# team13.net
KiCad netlist of a schematic drawn in EAGLE
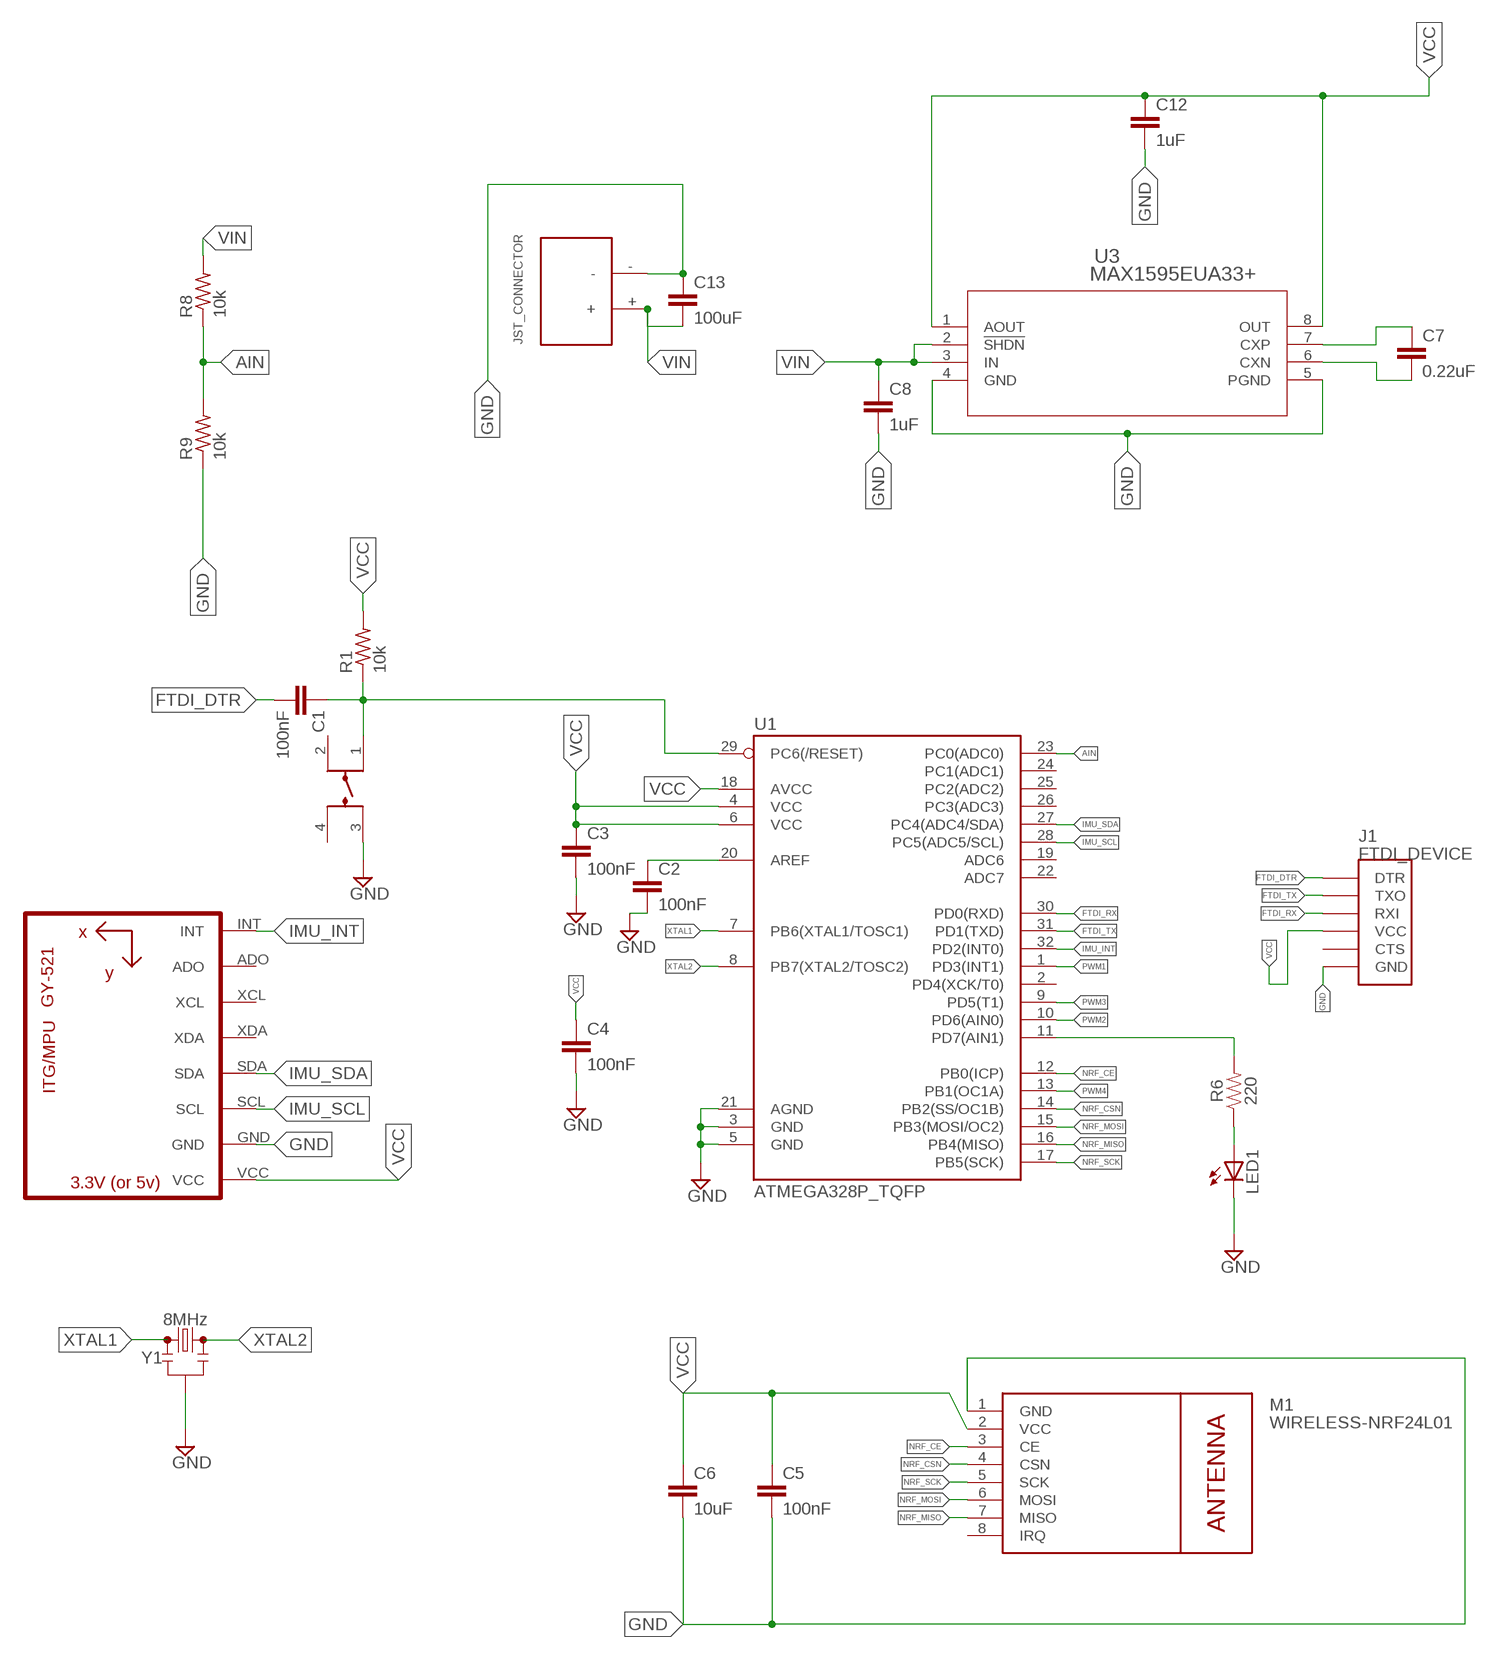
[diagram p0: schematic, sheet 1, part 1 of 3]
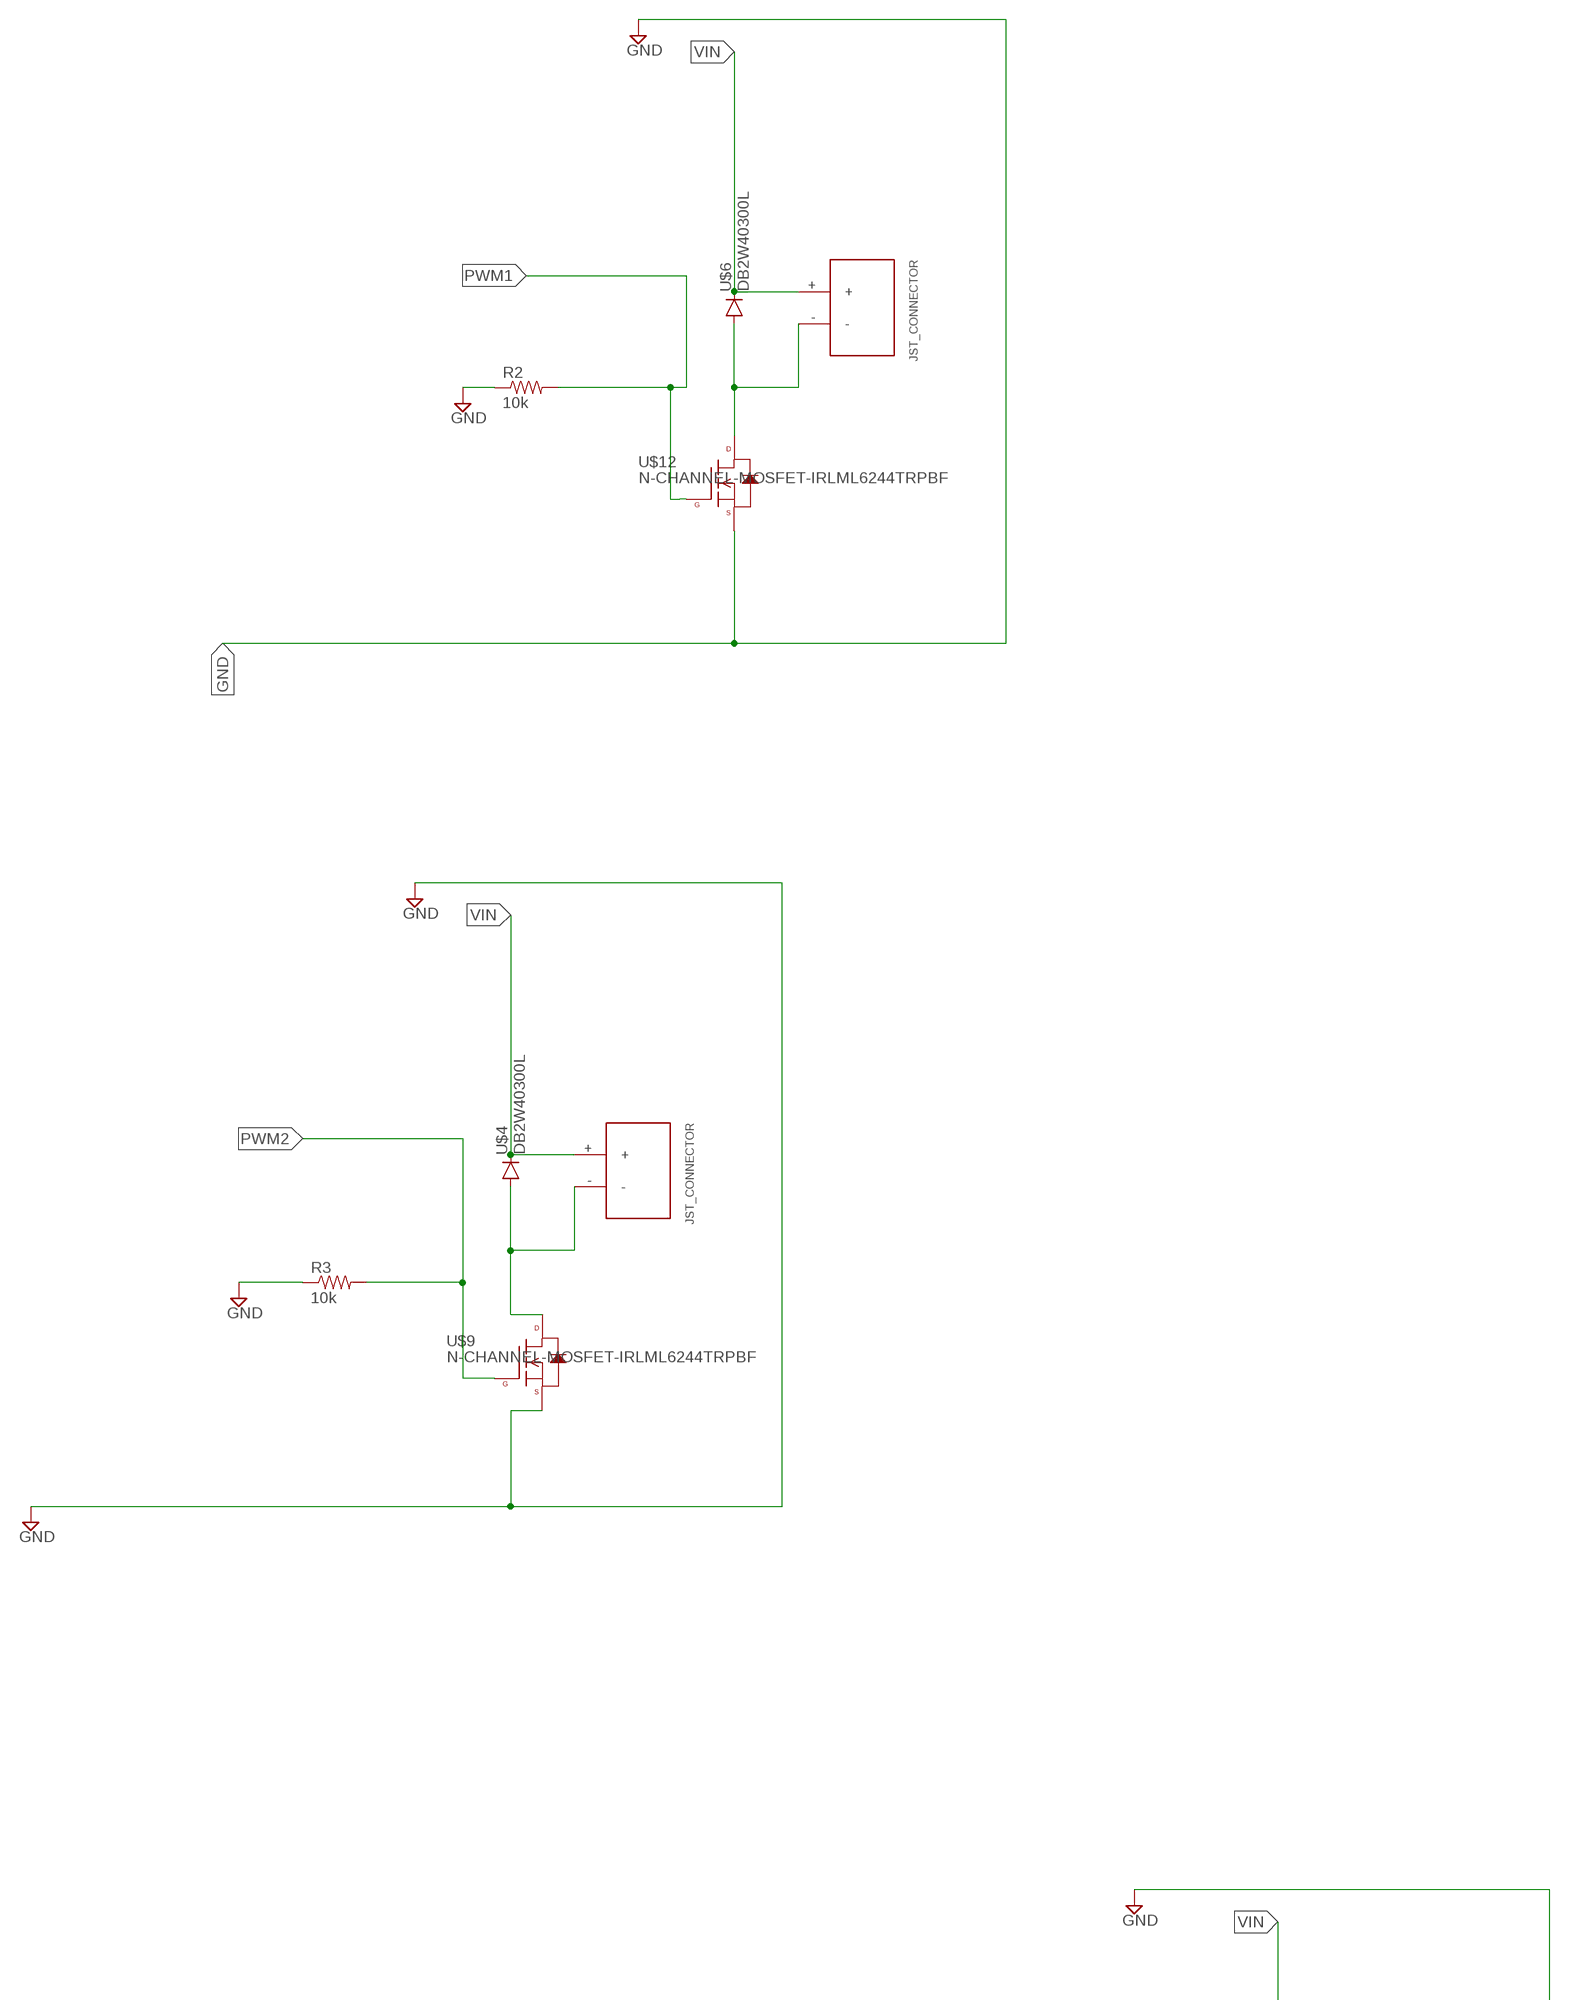
[diagram p1: schematic, sheet 1, part 2 of 3]
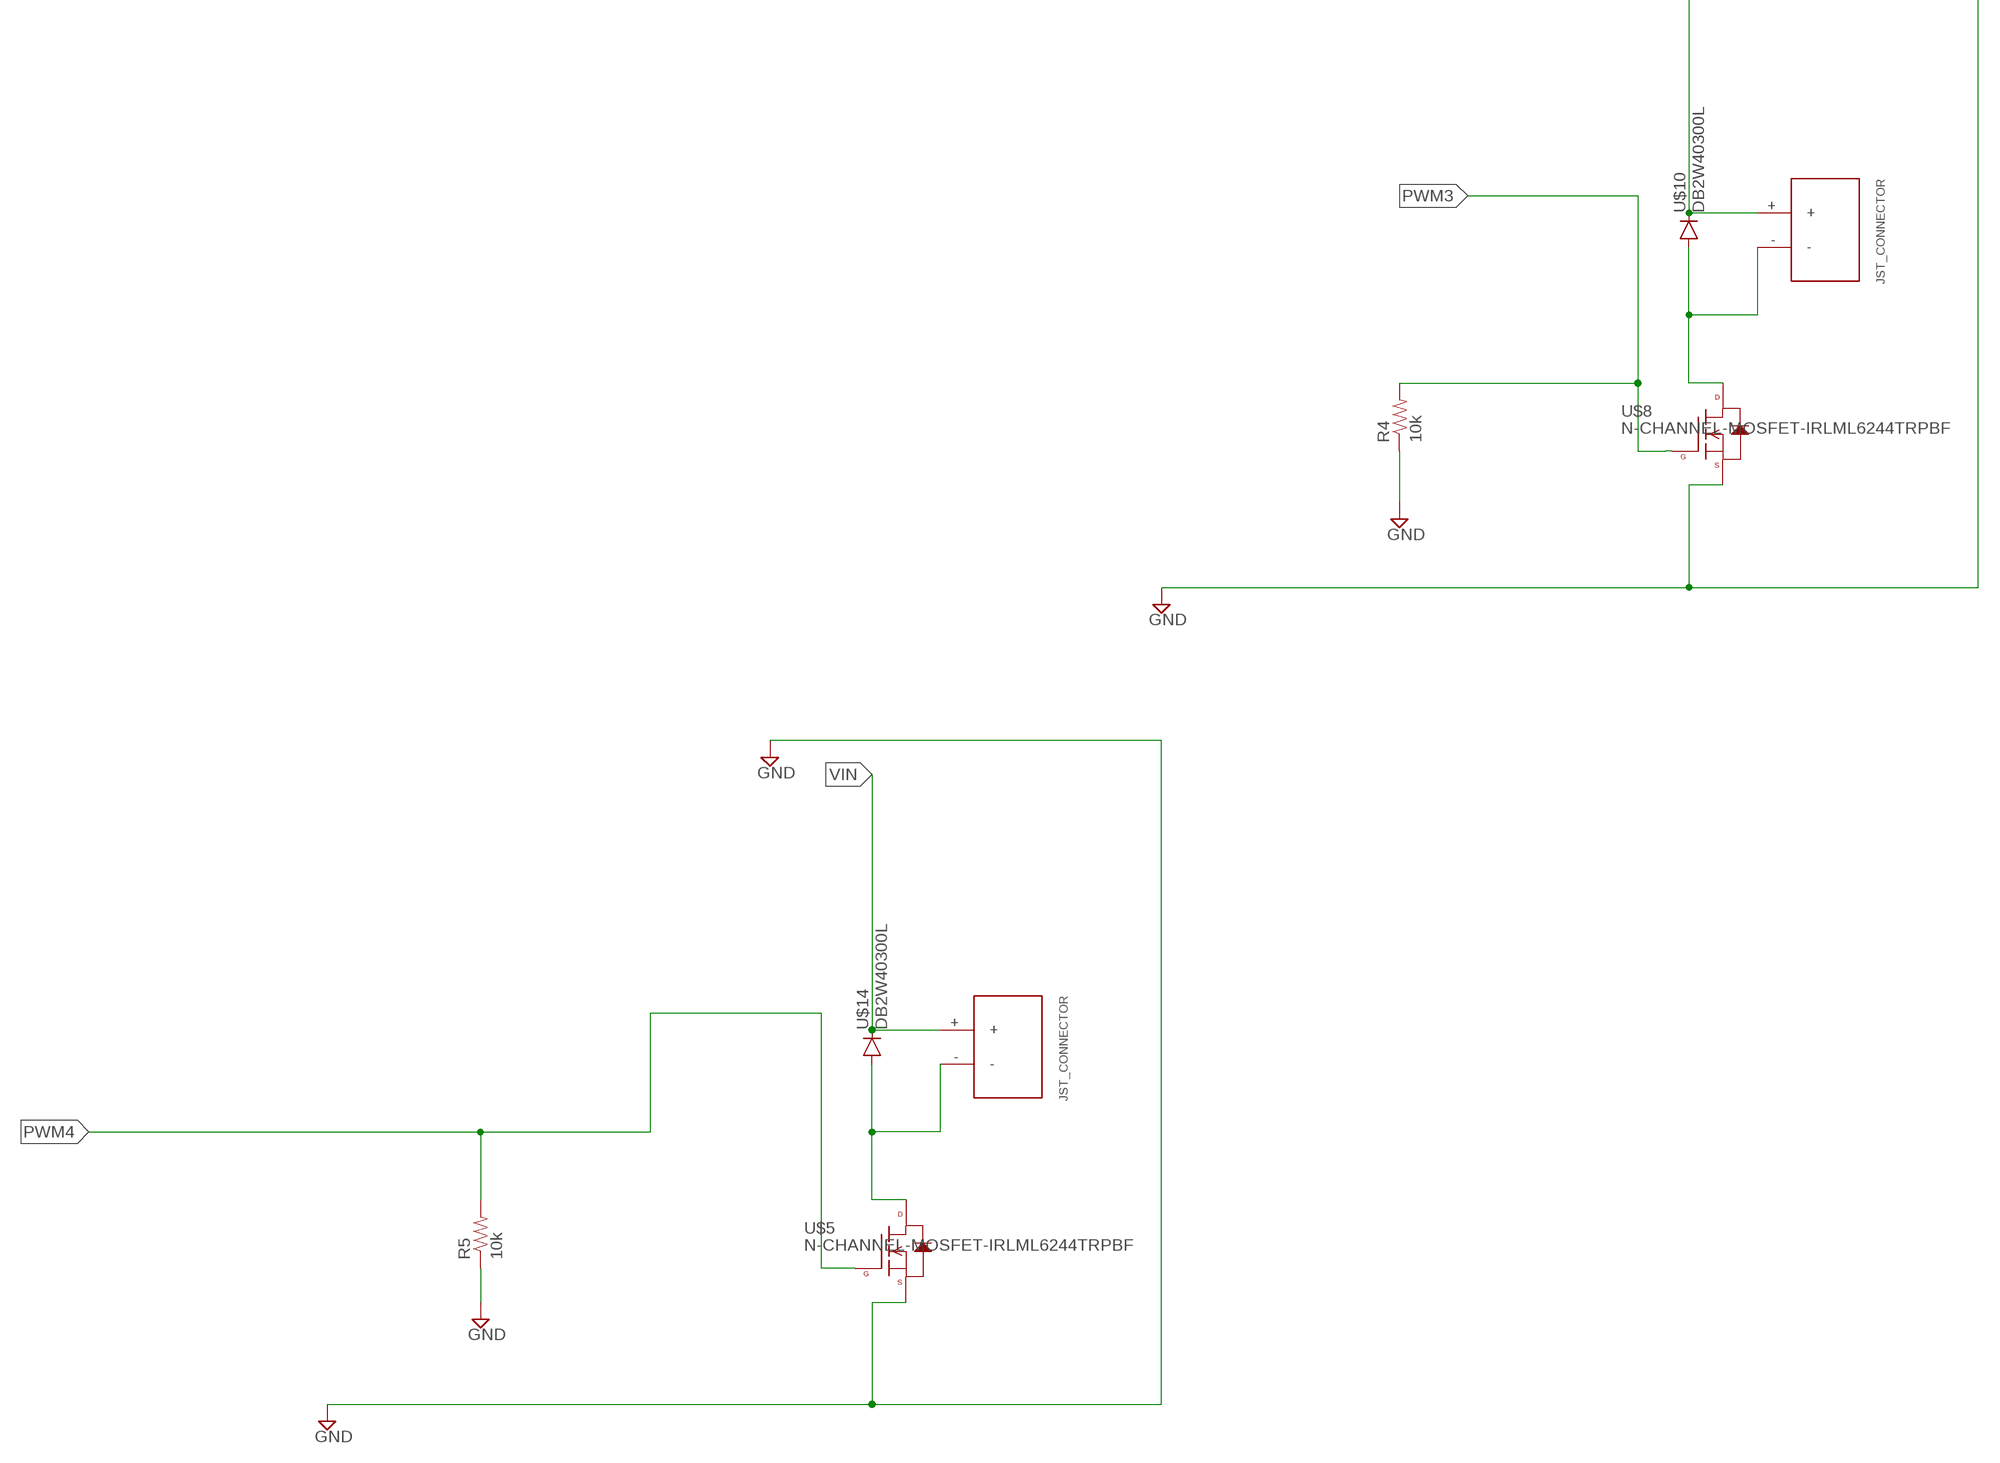
[diagram p2: schematic, sheet 1, part 3 of 3]

(export (version "E")
  (design (tool "Eeschema 10.0.6"))
  (components
    (comp (ref "C1")
      (value "100nF")
      (footprint "eagle-import:C0603")
      (libsource (lib "eagle-import") (part "C-EUC0603"))
    )
    (comp (ref "C2")
      (value "100nF")
      (footprint "eagle-import:C0603")
      (libsource (lib "eagle-import") (part "C-EUC0603"))
    )
    (comp (ref "C3")
      (value "100nF")
      (footprint "eagle-import:C0603")
      (libsource (lib "eagle-import") (part "C-EUC0603"))
    )
    (comp (ref "C4")
      (value "100nF")
      (footprint "eagle-import:C0603")
      (libsource (lib "eagle-import") (part "C-EUC0603"))
    )
    (comp (ref "C5")
      (value "100nF")
      (footprint "eagle-import:C0603")
      (libsource (lib "eagle-import") (part "C-EUC0603"))
    )
    (comp (ref "C6")
      (value "10uF")
      (footprint "eagle-import:C0603")
      (libsource (lib "eagle-import") (part "C-EUC0603"))
    )
    (comp (ref "C7")
      (value "0.22uF")
      (footprint "eagle-import:C0603")
      (libsource (lib "eagle-import") (part "C-EUC0603"))
    )
    (comp (ref "C8")
      (value "1uF")
      (footprint "eagle-import:C0603")
      (libsource (lib "eagle-import") (part "C-EUC0603"))
    )
    (comp (ref "C12")
      (value "1uF")
      (footprint "eagle-import:C0603")
      (libsource (lib "eagle-import") (part "C-EUC0603"))
    )
    (comp (ref "C13")
      (value "100uF")
      (footprint "eagle-import:C1206")
      (libsource (lib "eagle-import") (part "C-EUC1206"))
    )
    (comp (ref "J1")
      (value "FTDI_DEVICE")
      (footprint "eagle-import:FTDI_DEVICE_SIDE")
      (libsource (lib "eagle-import") (part "FTDI_DEVICE"))
    )
    (comp (ref "LED1")
      (value "LED1206")
      (footprint "eagle-import:LED-1206")
      (libsource (lib "eagle-import") (part "LED1206"))
    )
    (comp (ref "M1")
      (value "WIRELESS-NRF24L01")
      (footprint "eagle-import:WIRELESS-NRF24L01")
      (libsource (lib "eagle-import") (part "WIRELESS-NRF24L01"))
    )
    (comp (ref "R1")
      (value "10k")
      (footprint "eagle-import:R0603")
      (libsource (lib "eagle-import") (part "R-US_R0603"))
    )
    (comp (ref "R2")
      (value "10k")
      (footprint "eagle-import:0603-RES")
      (libsource (lib "eagle-import") (part "RESISTOR0603"))
    )
    (comp (ref "R3")
      (value "10k")
      (footprint "eagle-import:0603-RES")
      (libsource (lib "eagle-import") (part "RESISTOR0603"))
    )
    (comp (ref "R4")
      (value "10k")
      (footprint "eagle-import:0603-RES")
      (libsource (lib "eagle-import") (part "RESISTOR0603"))
    )
    (comp (ref "R5")
      (value "10k")
      (footprint "eagle-import:0603-RES")
      (libsource (lib "eagle-import") (part "RESISTOR0603"))
    )
    (comp (ref "R6")
      (value "220")
      (footprint "eagle-import:0603")
      (libsource (lib "eagle-import") (part "220OHM-0603-1/10W-1%"))
    )
    (comp (ref "R8")
      (value "10k")
      (footprint "eagle-import:R0603")
      (libsource (lib "eagle-import") (part "R-US_R0603"))
    )
    (comp (ref "R9")
      (value "10k")
      (footprint "eagle-import:R0603")
      (libsource (lib "eagle-import") (part "R-US_R0603"))
    )
    (comp (ref "U$1")
      (value "LL3301NF065QG")
      (footprint "eagle-import:LL3301NF065QG")
      (libsource (lib "eagle-import") (part "LL3301NF065QG"))
    )
    (comp (ref "U$3")
      (value "JST_CONNECTOR_FEMALE")
      (footprint "eagle-import:JST_CONNECTOR_FEMALE")
      (libsource (lib "eagle-import") (part "JST_CONNECTOR_FEMALE"))
    )
    (comp (ref "U$4")
      (value "DB2W40300L")
      (footprint "eagle-import:MINI2-F3-B")
      (libsource (lib "eagle-import") (part "DB2W40300L"))
    )
    (comp (ref "U$5")
      (value "N-CHANNEL-MOSFET-IRLML6244TRPBF")
      (footprint "eagle-import:SOT23-3")
      (libsource (lib "eagle-import") (part "N-CHANNEL-MOSFET-IRLML6244TRPBF"))
    )
    (comp (ref "U$6")
      (value "DB2W40300L")
      (footprint "eagle-import:MINI2-F3-B")
      (libsource (lib "eagle-import") (part "DB2W40300L"))
    )
    (comp (ref "U$7")
      (value "JST_CONNECTOR_FEMALE")
      (footprint "eagle-import:JST_CONNECTOR_FEMALE")
      (libsource (lib "eagle-import") (part "JST_CONNECTOR_FEMALE"))
    )
    (comp (ref "U$8")
      (value "N-CHANNEL-MOSFET-IRLML6244TRPBF")
      (footprint "eagle-import:SOT23-3")
      (libsource (lib "eagle-import") (part "N-CHANNEL-MOSFET-IRLML6244TRPBF"))
    )
    (comp (ref "U$9")
      (value "N-CHANNEL-MOSFET-IRLML6244TRPBF")
      (footprint "eagle-import:SOT23-3")
      (libsource (lib "eagle-import") (part "N-CHANNEL-MOSFET-IRLML6244TRPBF"))
    )
    (comp (ref "U$10")
      (value "DB2W40300L")
      (footprint "eagle-import:MINI2-F3-B")
      (libsource (lib "eagle-import") (part "DB2W40300L"))
    )
    (comp (ref "U$11")
      (value "JST_CONNECTOR_FEMALE")
      (footprint "eagle-import:JST_CONNECTOR_FEMALE")
      (libsource (lib "eagle-import") (part "JST_CONNECTOR_FEMALE"))
    )
    (comp (ref "U$12")
      (value "N-CHANNEL-MOSFET-IRLML6244TRPBF")
      (footprint "eagle-import:SOT23-3")
      (libsource (lib "eagle-import") (part "N-CHANNEL-MOSFET-IRLML6244TRPBF"))
    )
    (comp (ref "U$14")
      (value "DB2W40300L")
      (footprint "eagle-import:MINI2-F3-B")
      (libsource (lib "eagle-import") (part "DB2W40300L"))
    )
    (comp (ref "U$15")
      (value "JST_CONNECTOR_FEMALE")
      (footprint "eagle-import:JST_CONNECTOR_FEMALE")
      (libsource (lib "eagle-import") (part "JST_CONNECTOR_FEMALE"))
    )
    (comp (ref "U$19")
      (value "JST_CONNECTOR_FEMALE")
      (footprint "eagle-import:JST_CONNECTOR_FEMALE")
      (libsource (lib "eagle-import") (part "JST_CONNECTOR_FEMALE"))
    )
    (comp (ref "U1")
      (value "ATMEGA328P_TQFP")
      (footprint "eagle-import:TQFP32-08")
      (libsource (lib "eagle-import") (part "ATMEGA328P_TQFP"))
    )
    (comp (ref "U2")
      (value "GY-521MPU6050")
      (footprint "eagle-import:GY-521")
      (libsource (lib "eagle-import") (part "GY-521MPU6050"))
    )
    (comp (ref "U3")
      (value "MAX1595EUA33+")
      (footprint "eagle-import:21-0036K")
      (libsource (lib "eagle-import") (part "MAX1595EUA33+"))
    )
    (comp (ref "Y1")
      (value "8MHz")
      (footprint "eagle-import:RESONATOR-SMD-3.2X1.3")
      (libsource (lib "eagle-import") (part "RESONATOR-8MHZSMD_3.2X1.3"))
    )
  )
  (nets
    (net (code "1") (name "AIN") (class "Default")
      (node (ref "R8") (pin "1") (pinfunction "1_1") (pintype "passive"))
      (node (ref "R9") (pin "2") (pinfunction "2_2") (pintype "passive"))
      (node (ref "U1") (pin "23") (pinfunction "PC0(ADC0)_23") (pintype "bidirectional"))
    )
    (net (code "2") (name "FTDI_DTR") (class "Default")
      (node (ref "C1") (pin "2") (pinfunction "2_2") (pintype "passive"))
      (node (ref "J1") (pin "P$1") (pinfunction "DTR_P$1") (pintype "bidirectional"))
    )
    (net (code "3") (name "FTDI_RX") (class "Default")
      (node (ref "J1") (pin "P$3") (pinfunction "RXI_P$3") (pintype "bidirectional"))
      (node (ref "U1") (pin "30") (pinfunction "PD0(RXD)_30") (pintype "bidirectional"))
    )
    (net (code "4") (name "FTDI_TX") (class "Default")
      (node (ref "J1") (pin "P$2") (pinfunction "TXO_P$2") (pintype "bidirectional"))
      (node (ref "U1") (pin "31") (pinfunction "PD1(TXD)_31") (pintype "bidirectional"))
    )
    (net (code "5") (name "GND") (class "Default")
      (node (ref "C12") (pin "2") (pinfunction "2_2") (pintype "passive"))
      (node (ref "C13") (pin "1") (pinfunction "1_1") (pintype "passive"))
      (node (ref "C2") (pin "2") (pinfunction "2_2") (pintype "passive"))
      (node (ref "C3") (pin "2") (pinfunction "2_2") (pintype "passive"))
      (node (ref "C4") (pin "2") (pinfunction "2_2") (pintype "passive"))
      (node (ref "C5") (pin "2") (pinfunction "2_2") (pintype "passive"))
      (node (ref "C6") (pin "2") (pinfunction "2_2") (pintype "passive"))
      (node (ref "C8") (pin "2") (pinfunction "2_2") (pintype "passive"))
      (node (ref "J1") (pin "P$6") (pinfunction "GND_P$6") (pintype "bidirectional"))
      (node (ref "LED1") (pin "C") (pinfunction "C_C") (pintype "passive"))
      (node (ref "M1") (pin "1") (pinfunction "GND_1") (pintype "power_in"))
      (node (ref "R2") (pin "1") (pinfunction "1_1") (pintype "passive"))
      (node (ref "R3") (pin "1") (pinfunction "1_1") (pintype "passive"))
      (node (ref "R4") (pin "1") (pinfunction "1_1") (pintype "passive"))
      (node (ref "R5") (pin "1") (pinfunction "1_1") (pintype "passive"))
      (node (ref "R9") (pin "1") (pinfunction "1_1") (pintype "passive"))
      (node (ref "U$1") (pin "3") (pinfunction "3_3") (pintype "passive"))
      (node (ref "U$12") (pin "2") (pinfunction "S_2") (pintype "passive"))
      (node (ref "U$19") (pin "-") (pinfunction "-_-") (pintype "bidirectional"))
      (node (ref "U$5") (pin "2") (pinfunction "S_2") (pintype "passive"))
      (node (ref "U$8") (pin "2") (pinfunction "S_2") (pintype "passive"))
      (node (ref "U$9") (pin "2") (pinfunction "S_2") (pintype "passive"))
      (node (ref "U1") (pin "21") (pinfunction "AGND_21") (pintype "bidirectional"))
      (node (ref "U1") (pin "3") (pinfunction "GND_3") (pintype "bidirectional"))
      (node (ref "U1") (pin "5") (pinfunction "GND_5") (pintype "bidirectional"))
      (node (ref "U2") (pin "GND") (pinfunction "GND_GND") (pintype "bidirectional"))
      (node (ref "U3") (pin "4") (pinfunction "GND_4") (pintype "power_in"))
      (node (ref "U3") (pin "5") (pinfunction "PGND_5") (pintype "passive"))
      (node (ref "Y1") (pin "2") (pinfunction "2_2") (pintype "passive"))
    )
    (net (code "6") (name "IMU_INT") (class "Default")
      (node (ref "U1") (pin "32") (pinfunction "PD2(INT0)_32") (pintype "bidirectional"))
      (node (ref "U2") (pin "INT") (pinfunction "INT_INT") (pintype "bidirectional"))
    )
    (net (code "7") (name "IMU_SCL") (class "Default")
      (node (ref "U1") (pin "28") (pinfunction "PC5(ADC5/SCL)_28") (pintype "bidirectional"))
      (node (ref "U2") (pin "SCL") (pinfunction "SCL_SCL") (pintype "bidirectional"))
    )
    (net (code "8") (name "IMU_SDA") (class "Default")
      (node (ref "U1") (pin "27") (pinfunction "PC4(ADC4/SDA)_27") (pintype "bidirectional"))
      (node (ref "U2") (pin "SDA") (pinfunction "SDA_SDA") (pintype "bidirectional"))
    )
    (net (code "9") (name "NRF_CE") (class "Default")
      (node (ref "M1") (pin "3") (pinfunction "CE_3") (pintype "bidirectional"))
      (node (ref "U1") (pin "12") (pinfunction "PB0(ICP)_12") (pintype "bidirectional"))
    )
    (net (code "10") (name "NRF_CSN") (class "Default")
      (node (ref "M1") (pin "4") (pinfunction "CSN_4") (pintype "bidirectional"))
      (node (ref "U1") (pin "14") (pinfunction "PB2(SS/OC1B)_14") (pintype "bidirectional"))
    )
    (net (code "11") (name "NRF_MISO") (class "Default")
      (node (ref "M1") (pin "7") (pinfunction "MISO_7") (pintype "bidirectional"))
      (node (ref "U1") (pin "16") (pinfunction "PB4(MISO)_16") (pintype "bidirectional"))
    )
    (net (code "12") (name "NRF_MOSI") (class "Default")
      (node (ref "M1") (pin "6") (pinfunction "MOSI_6") (pintype "bidirectional"))
      (node (ref "U1") (pin "15") (pinfunction "PB3(MOSI/OC2)_15") (pintype "bidirectional"))
    )
    (net (code "13") (name "NRF_SCK") (class "Default")
      (node (ref "M1") (pin "5") (pinfunction "SCK_5") (pintype "bidirectional"))
      (node (ref "U1") (pin "17") (pinfunction "PB5(SCK)_17") (pintype "bidirectional"))
    )
    (net (code "14") (name "Net-(LED1-PadA)") (class "Default")
      (node (ref "LED1") (pin "A") (pinfunction "A_A") (pintype "passive"))
      (node (ref "R6") (pin "1") (pinfunction "1_1") (pintype "passive"))
    )
    (net (code "15") (name "Net-(U$4-PPIN)") (class "Default")
      (node (ref "U$3") (pin "-") (pinfunction "-_-") (pintype "bidirectional"))
      (node (ref "U$4") (pin "POS") (pinfunction "PPIN_POS") (pintype "passive"))
      (node (ref "U$9") (pin "3") (pinfunction "D_3") (pintype "passive"))
    )
    (net (code "16") (name "Net-(U$10-PPIN)") (class "Default")
      (node (ref "U$10") (pin "POS") (pinfunction "PPIN_POS") (pintype "passive"))
      (node (ref "U$11") (pin "-") (pinfunction "-_-") (pintype "bidirectional"))
      (node (ref "U$8") (pin "3") (pinfunction "D_3") (pintype "passive"))
    )
    (net (code "17") (name "Net-(U$12-D)") (class "Default")
      (node (ref "U$12") (pin "3") (pinfunction "D_3") (pintype "passive"))
      (node (ref "U$6") (pin "POS") (pinfunction "PPIN_POS") (pintype "passive"))
      (node (ref "U$7") (pin "-") (pinfunction "-_-") (pintype "bidirectional"))
    )
    (net (code "18") (name "Net-(U$14-PPIN)") (class "Default")
      (node (ref "U$14") (pin "POS") (pinfunction "PPIN_POS") (pintype "passive"))
      (node (ref "U$15") (pin "-") (pinfunction "-_-") (pintype "bidirectional"))
      (node (ref "U$5") (pin "3") (pinfunction "D_3") (pintype "passive"))
    )
    (net (code "19") (name "Net-(U1-AREF)") (class "Default")
      (node (ref "C2") (pin "1") (pinfunction "1_1") (pintype "passive"))
      (node (ref "U1") (pin "20") (pinfunction "AREF_20") (pintype "bidirectional"))
    )
    (net (code "20") (name "Net-(U1-PC6({slash}RESET))") (class "Default")
      (node (ref "C1") (pin "1") (pinfunction "1_1") (pintype "passive"))
      (node (ref "R1") (pin "1") (pinfunction "1_1") (pintype "passive"))
      (node (ref "U$1") (pin "1") (pinfunction "1_1") (pintype "passive"))
      (node (ref "U1") (pin "29") (pinfunction "PC6(/RESET)_29") (pintype "bidirectional"))
    )
    (net (code "21") (name "Net-(U1-PD7(AIN1))") (class "Default")
      (node (ref "R6") (pin "2") (pinfunction "2_2") (pintype "passive"))
      (node (ref "U1") (pin "11") (pinfunction "PD7(AIN1)_11") (pintype "bidirectional"))
    )
    (net (code "22") (name "Net-(U3-CXN)") (class "Default")
      (node (ref "C7") (pin "2") (pinfunction "2_2") (pintype "passive"))
      (node (ref "U3") (pin "6") (pinfunction "CXN_6") (pintype "passive"))
    )
    (net (code "23") (name "Net-(U3-CXP)") (class "Default")
      (node (ref "C7") (pin "1") (pinfunction "1_1") (pintype "passive"))
      (node (ref "U3") (pin "7") (pinfunction "CXP_7") (pintype "passive"))
    )
    (net (code "24") (name "PWM1") (class "Default")
      (node (ref "R2") (pin "2") (pinfunction "2_2") (pintype "passive"))
      (node (ref "U$12") (pin "1") (pinfunction "G_1") (pintype "passive"))
      (node (ref "U1") (pin "1") (pinfunction "PD3(INT1)_1") (pintype "bidirectional"))
    )
    (net (code "25") (name "PWM2") (class "Default")
      (node (ref "R3") (pin "2") (pinfunction "2_2") (pintype "passive"))
      (node (ref "U$9") (pin "1") (pinfunction "G_1") (pintype "passive"))
      (node (ref "U1") (pin "10") (pinfunction "PD6(AIN0)_10") (pintype "bidirectional"))
    )
    (net (code "26") (name "PWM3") (class "Default")
      (node (ref "R4") (pin "2") (pinfunction "2_2") (pintype "passive"))
      (node (ref "U$8") (pin "1") (pinfunction "G_1") (pintype "passive"))
      (node (ref "U1") (pin "9") (pinfunction "PD5(T1)_9") (pintype "bidirectional"))
    )
    (net (code "27") (name "PWM4") (class "Default")
      (node (ref "R5") (pin "2") (pinfunction "2_2") (pintype "passive"))
      (node (ref "U$5") (pin "1") (pinfunction "G_1") (pintype "passive"))
      (node (ref "U1") (pin "13") (pinfunction "PB1(OC1A)_13") (pintype "bidirectional"))
    )
    (net (code "28") (name "VCC") (class "Default")
      (node (ref "C12") (pin "1") (pinfunction "1_1") (pintype "passive"))
      (node (ref "C3") (pin "1") (pinfunction "1_1") (pintype "passive"))
      (node (ref "C4") (pin "1") (pinfunction "1_1") (pintype "passive"))
      (node (ref "C5") (pin "1") (pinfunction "1_1") (pintype "passive"))
      (node (ref "C6") (pin "1") (pinfunction "1_1") (pintype "passive"))
      (node (ref "J1") (pin "P$4") (pinfunction "VCC_P$4") (pintype "bidirectional"))
      (node (ref "M1") (pin "2") (pinfunction "VCC_2") (pintype "power_in"))
      (node (ref "R1") (pin "2") (pinfunction "2_2") (pintype "passive"))
      (node (ref "U1") (pin "18") (pinfunction "AVCC_18") (pintype "bidirectional"))
      (node (ref "U1") (pin "4") (pinfunction "VCC_4") (pintype "bidirectional"))
      (node (ref "U1") (pin "6") (pinfunction "VCC_6") (pintype "bidirectional"))
      (node (ref "U2") (pin "VCC") (pinfunction "VCC_VCC") (pintype "bidirectional"))
      (node (ref "U3") (pin "1") (pinfunction "AOUT_1") (pintype "passive"))
      (node (ref "U3") (pin "8") (pinfunction "OUT_8") (pintype "passive"))
    )
    (net (code "29") (name "VIN") (class "Default")
      (node (ref "C13") (pin "2") (pinfunction "2_2") (pintype "passive"))
      (node (ref "C8") (pin "1") (pinfunction "1_1") (pintype "passive"))
      (node (ref "R8") (pin "2") (pinfunction "2_2") (pintype "passive"))
      (node (ref "U$10") (pin "NEG") (pinfunction "GPIN_NEG") (pintype "passive"))
      (node (ref "U$11") (pin "+") (pinfunction "+_+") (pintype "bidirectional"))
      (node (ref "U$14") (pin "NEG") (pinfunction "GPIN_NEG") (pintype "passive"))
      (node (ref "U$15") (pin "+") (pinfunction "+_+") (pintype "bidirectional"))
      (node (ref "U$19") (pin "+") (pinfunction "+_+") (pintype "bidirectional"))
      (node (ref "U$3") (pin "+") (pinfunction "+_+") (pintype "bidirectional"))
      (node (ref "U$4") (pin "NEG") (pinfunction "GPIN_NEG") (pintype "passive"))
      (node (ref "U$6") (pin "NEG") (pinfunction "GPIN_NEG") (pintype "passive"))
      (node (ref "U$7") (pin "+") (pinfunction "+_+") (pintype "bidirectional"))
      (node (ref "U3") (pin "2") (pinfunction "~{SHDN}_2") (pintype "passive"))
      (node (ref "U3") (pin "3") (pinfunction "IN_3") (pintype "input"))
    )
    (net (code "30") (name "XTAL1") (class "Default")
      (node (ref "U1") (pin "7") (pinfunction "PB6(XTAL1/TOSC1)_7") (pintype "bidirectional"))
      (node (ref "Y1") (pin "1") (pinfunction "1_1") (pintype "passive"))
    )
    (net (code "31") (name "XTAL2") (class "Default")
      (node (ref "U1") (pin "8") (pinfunction "PB7(XTAL2/TOSC2)_8") (pintype "bidirectional"))
      (node (ref "Y1") (pin "3") (pinfunction "3_3") (pintype "passive"))
    )
    (net (code "32") (name "unconnected-(J1-CTS-PadP$5)") (class "Default")
      (node (ref "J1") (pin "P$5") (pinfunction "CTS_P$5") (pintype "bidirectional"))
    )
    (net (code "33") (name "unconnected-(M1-IRQ-Pad8)") (class "Default")
      (node (ref "M1") (pin "8") (pinfunction "IRQ_8") (pintype "bidirectional"))
    )
    (net (code "34") (name "unconnected-(U$1-Pad2)") (class "Default")
      (node (ref "U$1") (pin "2") (pinfunction "2_2") (pintype "passive"))
    )
    (net (code "35") (name "unconnected-(U$1-Pad4)") (class "Default")
      (node (ref "U$1") (pin "4") (pinfunction "4_4") (pintype "passive"))
    )
    (net (code "36") (name "unconnected-(U1-ADC6-Pad19)") (class "Default")
      (node (ref "U1") (pin "19") (pinfunction "ADC6_19") (pintype "bidirectional"))
    )
    (net (code "37") (name "unconnected-(U1-ADC7-Pad22)") (class "Default")
      (node (ref "U1") (pin "22") (pinfunction "ADC7_22") (pintype "bidirectional"))
    )
    (net (code "38") (name "unconnected-(U1-PC1(ADC1)-Pad24)") (class "Default")
      (node (ref "U1") (pin "24") (pinfunction "PC1(ADC1)_24") (pintype "bidirectional"))
    )
    (net (code "39") (name "unconnected-(U1-PC2(ADC2)-Pad25)") (class "Default")
      (node (ref "U1") (pin "25") (pinfunction "PC2(ADC2)_25") (pintype "bidirectional"))
    )
    (net (code "40") (name "unconnected-(U1-PC3(ADC3)-Pad26)") (class "Default")
      (node (ref "U1") (pin "26") (pinfunction "PC3(ADC3)_26") (pintype "bidirectional"))
    )
    (net (code "41") (name "unconnected-(U1-PD4(XCK{slash}T0)-Pad2)") (class "Default")
      (node (ref "U1") (pin "2") (pinfunction "PD4(XCK/T0)_2") (pintype "bidirectional"))
    )
    (net (code "42") (name "unconnected-(U2-PadADO)") (class "Default")
      (node (ref "U2") (pin "ADO") (pinfunction "ADO_ADO") (pintype "bidirectional"))
    )
    (net (code "43") (name "unconnected-(U2-PadXCL)") (class "Default")
      (node (ref "U2") (pin "XCL") (pinfunction "XCL_XCL") (pintype "bidirectional"))
    )
    (net (code "44") (name "unconnected-(U2-PadXDA)") (class "Default")
      (node (ref "U2") (pin "XDA") (pinfunction "XDA_XDA") (pintype "bidirectional"))
    )
  )
)
